# TPS54561_Buck_HV.net
KiCad netlist of a schematic drawn in Altium Designer
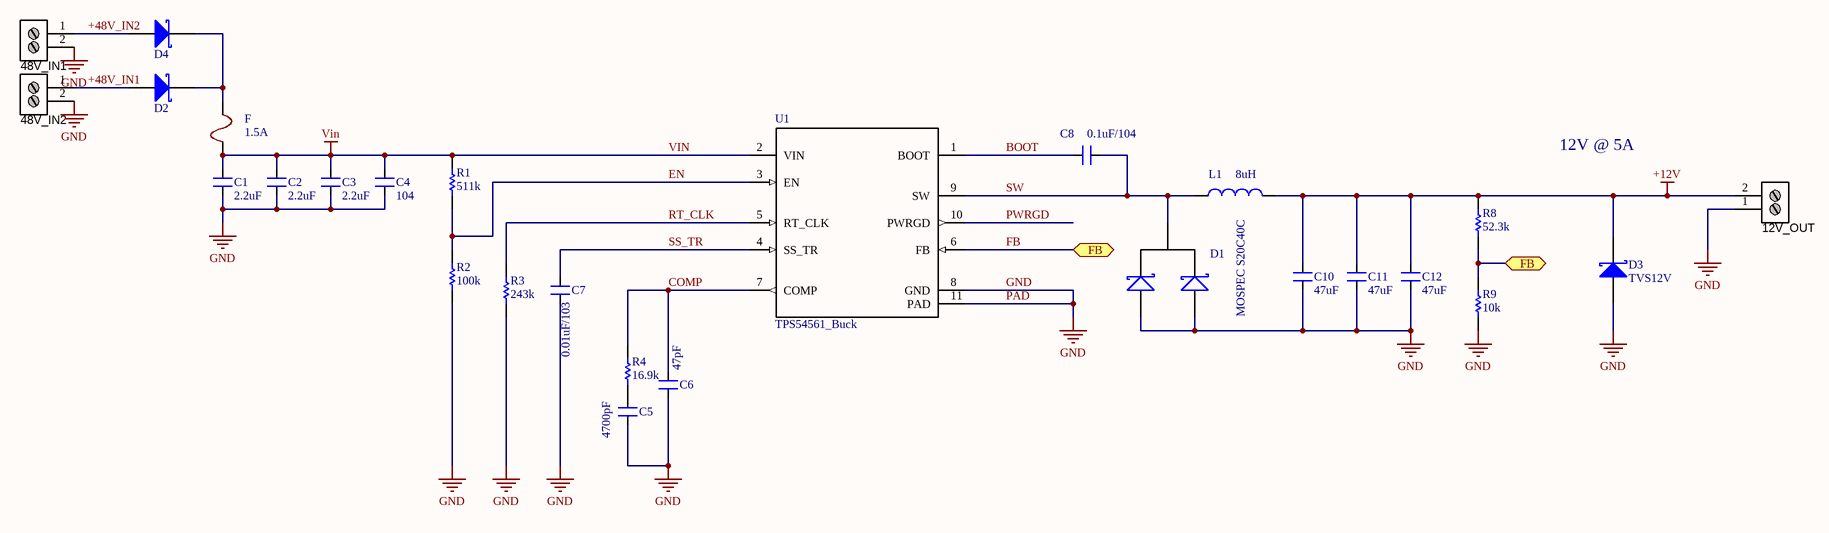
[diagram p0: TPS54561_Buck_HV.SchDoc]

(export (version "E")
  (design (tool "Eeschema 10.0.6"))
  (components
    (comp (ref "12V_OUT")
      (value "Stackable ScrewTerm")
      (footprint "2P_PCB_ScrewTerm_200mil")
      (description "Terminal Block Screw Type THT 2-Position 3.81mm pitch")
      (libsource (lib "") (part "2P_ScrewTerm_90S_3.81MM_1"))
    )
    (comp (ref "48V_IN1")
      (value "Stackable ScrewTerm")
      (footprint "2P_PCB_ScrewTerm_200mil")
      (description "Terminal Block Screw Type THT 2-Position 3.81mm pitch")
      (libsource (lib "PBL - Connectors") (part "2P_ScrewTerm_90S_3.81MM"))
    )
    (comp (ref "48V_IN2")
      (value "Stackable ScrewTerm")
      (footprint "2P_PCB_ScrewTerm_200mil")
      (description "Terminal Block Screw Type THT 2-Position 3.81mm pitch")
      (libsource (lib "PBL - Connectors") (part "2P_ScrewTerm_90S_3.81MM"))
    )
    (comp (ref "C1")
      (value "2.2uF")
      (footprint "CAPC3225N")
      (fields (field (name "Comment") "CAP NP"))
      (libsource (lib "Tuan") (part "CAP NP"))
    )
    (comp (ref "C2")
      (value "2.2uF")
      (footprint "CAPC3225N")
      (fields (field (name "Comment") "CAP NP"))
      (libsource (lib "Tuan") (part "CAP NP"))
    )
    (comp (ref "C3")
      (value "2.2uF")
      (footprint "CAPC3225N")
      (fields (field (name "Comment") "CAP NP"))
      (libsource (lib "Tuan") (part "CAP NP"))
    )
    (comp (ref "C4")
      (value "104")
      (footprint "CAPC1608N")
      (fields (field (name "Comment") "CAP NP"))
      (libsource (lib "Tuan") (part "CAP NP"))
    )
    (comp (ref "C5")
      (value "4700pF")
      (footprint "CAPC2012N")
      (fields (field (name "Comment") "CAP NP"))
      (libsource (lib "Tuan") (part "CAP NP"))
    )
    (comp (ref "C6")
      (value "47pF")
      (footprint "CAPC2012N")
      (fields (field (name "Comment") "CAP NP"))
      (libsource (lib "Tuan") (part "CAP NP"))
    )
    (comp (ref "C7")
      (value "0.01uF/103")
      (footprint "CAPC2012N_F")
      (fields (field (name "Comment") "CAP NP"))
      (libsource (lib "Tuan") (part "CAP NP"))
    )
    (comp (ref "C8")
      (value "0.1uF/104")
      (footprint "CAPC1608N_F")
      (fields (field (name "Comment") "CAP NP"))
      (libsource (lib "Tuan") (part "CAP NP"))
    )
    (comp (ref "C10")
      (value "47uF")
      (footprint "CAPC3225N")
      (fields (field (name "Comment") "CAP NP"))
      (libsource (lib "Tuan") (part "CAP NP"))
    )
    (comp (ref "C11")
      (value "47uF")
      (footprint "CAPC3225N")
      (fields (field (name "Comment") "CAP NP"))
      (libsource (lib "Tuan") (part "CAP NP"))
    )
    (comp (ref "C12")
      (value "47uF")
      (footprint "CAPC3225N")
      (fields (field (name "Comment") "CAP NP"))
      (libsource (lib "Tuan") (part "CAP NP"))
    )
    (comp (ref "D1") (value "MOSPEC S20C40C") (footprint "TO-220") (libsource (lib "Tuan") (part "Diode x2")))
    (comp (ref "D2") (value "~") (footprint "DO-214AC") (libsource (lib "Tuan") (part "Diode Schottky")))
    (comp (ref "D3") (value "TVS12V") (footprint "DO-214AA") (libsource (lib "Tuan") (part "Diode Schottky")))
    (comp (ref "D4") (value "SS14") (footprint "DO-214AC") (libsource (lib "Tuan") (part "Diode Schottky")))
    (comp (ref "F") (value "1.5A") (footprint "FUSE_SR-5-BK") (libsource (lib "Tuan") (part "Fuse")))
    (comp (ref "L1")
      (value "8uH")
      (footprint "Toroid")
      (fields (field (name "Comment") "Inductor"))
      (libsource (lib "Tuan") (part "Inductor"))
    )
    (comp (ref "R1")
      (value "511k")
      (footprint "RESC2012N")
      (fields (field (name "Comment") "Res"))
      (libsource (lib "Tuan") (part "Res"))
    )
    (comp (ref "R2")
      (value "100k")
      (footprint "RESC2012N")
      (fields (field (name "Comment") "Res"))
      (libsource (lib "Tuan") (part "Res"))
    )
    (comp (ref "R3")
      (value "243k")
      (footprint "RESC2012N_F")
      (fields (field (name "Comment") "Res"))
      (libsource (lib "Tuan") (part "Res"))
    )
    (comp (ref "R4")
      (value "16.9k")
      (footprint "RESC2012N")
      (fields (field (name "Comment") "Res"))
      (libsource (lib "Tuan") (part "Res"))
    )
    (comp (ref "R8")
      (value "52.3k")
      (footprint "RESC2012N")
      (fields (field (name "Comment") "Res"))
      (libsource (lib "Tuan") (part "Res"))
    )
    (comp (ref "R9")
      (value "10k")
      (footprint "RESC2012N")
      (fields (field (name "Comment") "Res"))
      (libsource (lib "Tuan") (part "Res"))
    )
    (comp (ref "U1")
      (value "TPS54561_Buck")
      (footprint "DPR0010A")
      (libsource (lib "Tuan") (part "TPS54561_Buck"))
    )
  )
  (nets
    (net (code "1") (name "+12V") (class "Default")
      (node (ref "12V_OUT") (pin "2") (pinfunction "2_2") (pintype "passive"))
      (node (ref "C10") (pin "2") (pinfunction "2_2") (pintype "passive"))
      (node (ref "C11") (pin "2") (pinfunction "2_2") (pintype "passive"))
      (node (ref "C12") (pin "2") (pinfunction "2_2") (pintype "passive"))
      (node (ref "D3") (pin "2") (pinfunction "K_2") (pintype "passive"))
      (node (ref "L1") (pin "2") (pinfunction "2_2") (pintype "passive"))
      (node (ref "R8") (pin "2") (pinfunction "2_2") (pintype "passive"))
    )
    (net (code "2") (name "/+48V_IN1") (class "Default")
      (node (ref "48V_IN2") (pin "1") (pinfunction "1_1") (pintype "passive"))
      (node (ref "D2") (pin "1") (pinfunction "A_1") (pintype "passive"))
    )
    (net (code "3") (name "/+48V_IN2") (class "Default")
      (node (ref "48V_IN1") (pin "1") (pinfunction "1_1") (pintype "passive"))
      (node (ref "D4") (pin "1") (pinfunction "A_1") (pintype "passive"))
    )
    (net (code "4") (name "/BOOT") (class "Default")
      (node (ref "C8") (pin "2") (pinfunction "2_2") (pintype "passive"))
      (node (ref "U1") (pin "1") (pinfunction "BOOT_1") (pintype "power_in"))
    )
    (net (code "5") (name "/COMP") (class "Default")
      (node (ref "C6") (pin "1") (pinfunction "1_1") (pintype "passive"))
      (node (ref "R4") (pin "2") (pinfunction "2_2") (pintype "passive"))
      (node (ref "U1") (pin "7") (pinfunction "COMP_7") (pintype "output"))
    )
    (net (code "6") (name "/EN") (class "Default")
      (node (ref "R1") (pin "1") (pinfunction "1_1") (pintype "passive"))
      (node (ref "R2") (pin "2") (pinfunction "2_2") (pintype "passive"))
      (node (ref "U1") (pin "3") (pinfunction "EN_3") (pintype "input"))
    )
    (net (code "7") (name "/FB") (class "Default")
      (node (ref "R8") (pin "1") (pinfunction "1_1") (pintype "passive"))
      (node (ref "R9") (pin "2") (pinfunction "2_2") (pintype "passive"))
      (node (ref "U1") (pin "6") (pinfunction "FB_6") (pintype "input"))
    )
    (net (code "8") (name "/PWRGD") (class "Default")
      (node (ref "U1") (pin "10") (pinfunction "PWRGD_10") (pintype "output"))
    )
    (net (code "9") (name "/RT_CLK") (class "Default")
      (node (ref "R3") (pin "2") (pinfunction "2_2") (pintype "passive"))
      (node (ref "U1") (pin "5") (pinfunction "RT_CLK_5") (pintype "input"))
    )
    (net (code "10") (name "/SS_TR") (class "Default")
      (node (ref "C7") (pin "1") (pinfunction "1_1") (pintype "passive"))
      (node (ref "U1") (pin "4") (pinfunction "SS_TR_4") (pintype "input"))
    )
    (net (code "11") (name "/SW") (class "Default")
      (node (ref "C8") (pin "1") (pinfunction "1_1") (pintype "passive"))
      (node (ref "D1") (pin "2") (pinfunction "A2_2") (pintype "passive"))
      (node (ref "L1") (pin "1") (pinfunction "1_1") (pintype "passive"))
      (node (ref "U1") (pin "9") (pinfunction "SW_9") (pintype "power_in"))
    )
    (net (code "12") (name "GND") (class "Default")
      (node (ref "12V_OUT") (pin "1") (pinfunction "1_1") (pintype "passive"))
      (node (ref "48V_IN1") (pin "2") (pinfunction "2_2") (pintype "passive"))
      (node (ref "48V_IN2") (pin "2") (pinfunction "2_2") (pintype "passive"))
      (node (ref "C1") (pin "1") (pinfunction "1_1") (pintype "passive"))
      (node (ref "C10") (pin "1") (pinfunction "1_1") (pintype "passive"))
      (node (ref "C11") (pin "1") (pinfunction "1_1") (pintype "passive"))
      (node (ref "C12") (pin "1") (pinfunction "1_1") (pintype "passive"))
      (node (ref "C2") (pin "1") (pinfunction "1_1") (pintype "passive"))
      (node (ref "C3") (pin "1") (pinfunction "1_1") (pintype "passive"))
      (node (ref "C4") (pin "1") (pinfunction "1_1") (pintype "passive"))
      (node (ref "C5") (pin "1") (pinfunction "1_1") (pintype "passive"))
      (node (ref "C6") (pin "2") (pinfunction "2_2") (pintype "passive"))
      (node (ref "C7") (pin "2") (pinfunction "2_2") (pintype "passive"))
      (node (ref "D1") (pin "1") (pinfunction "A1_1") (pintype "passive"))
      (node (ref "D1") (pin "3") (pinfunction "K_3") (pintype "passive"))
      (node (ref "D3") (pin "1") (pinfunction "A_1") (pintype "passive"))
      (node (ref "R2") (pin "1") (pinfunction "1_1") (pintype "passive"))
      (node (ref "R3") (pin "1") (pinfunction "1_1") (pintype "passive"))
      (node (ref "R9") (pin "1") (pinfunction "1_1") (pintype "passive"))
      (node (ref "U1") (pin "11") (pinfunction "PAD_11") (pintype "power_in"))
      (node (ref "U1") (pin "8") (pinfunction "GND_8") (pintype "power_in"))
    )
    (net (code "13") (name "Net-(C5-Pad2)") (class "Default")
      (node (ref "C5") (pin "2") (pinfunction "2_2") (pintype "passive"))
      (node (ref "R4") (pin "1") (pinfunction "1_1") (pintype "passive"))
    )
    (net (code "14") (name "Net-(D2-K)") (class "Default")
      (node (ref "D2") (pin "2") (pinfunction "K_2") (pintype "passive"))
      (node (ref "D4") (pin "2") (pinfunction "K_2") (pintype "passive"))
      (node (ref "F") (pin "2") (pinfunction "2_2") (pintype "passive"))
    )
    (net (code "15") (name "Vin") (class "Default")
      (node (ref "C1") (pin "2") (pinfunction "2_2") (pintype "passive"))
      (node (ref "C2") (pin "2") (pinfunction "2_2") (pintype "passive"))
      (node (ref "C3") (pin "2") (pinfunction "2_2") (pintype "passive"))
      (node (ref "C4") (pin "2") (pinfunction "2_2") (pintype "passive"))
      (node (ref "F") (pin "1") (pinfunction "1_1") (pintype "passive"))
      (node (ref "R1") (pin "2") (pinfunction "2_2") (pintype "passive"))
      (node (ref "U1") (pin "2") (pinfunction "VIN_2") (pintype "power_in"))
    )
  )
)
